# switch-QPC1022.net
KiCad netlist of a schematic drawn in EAGLE
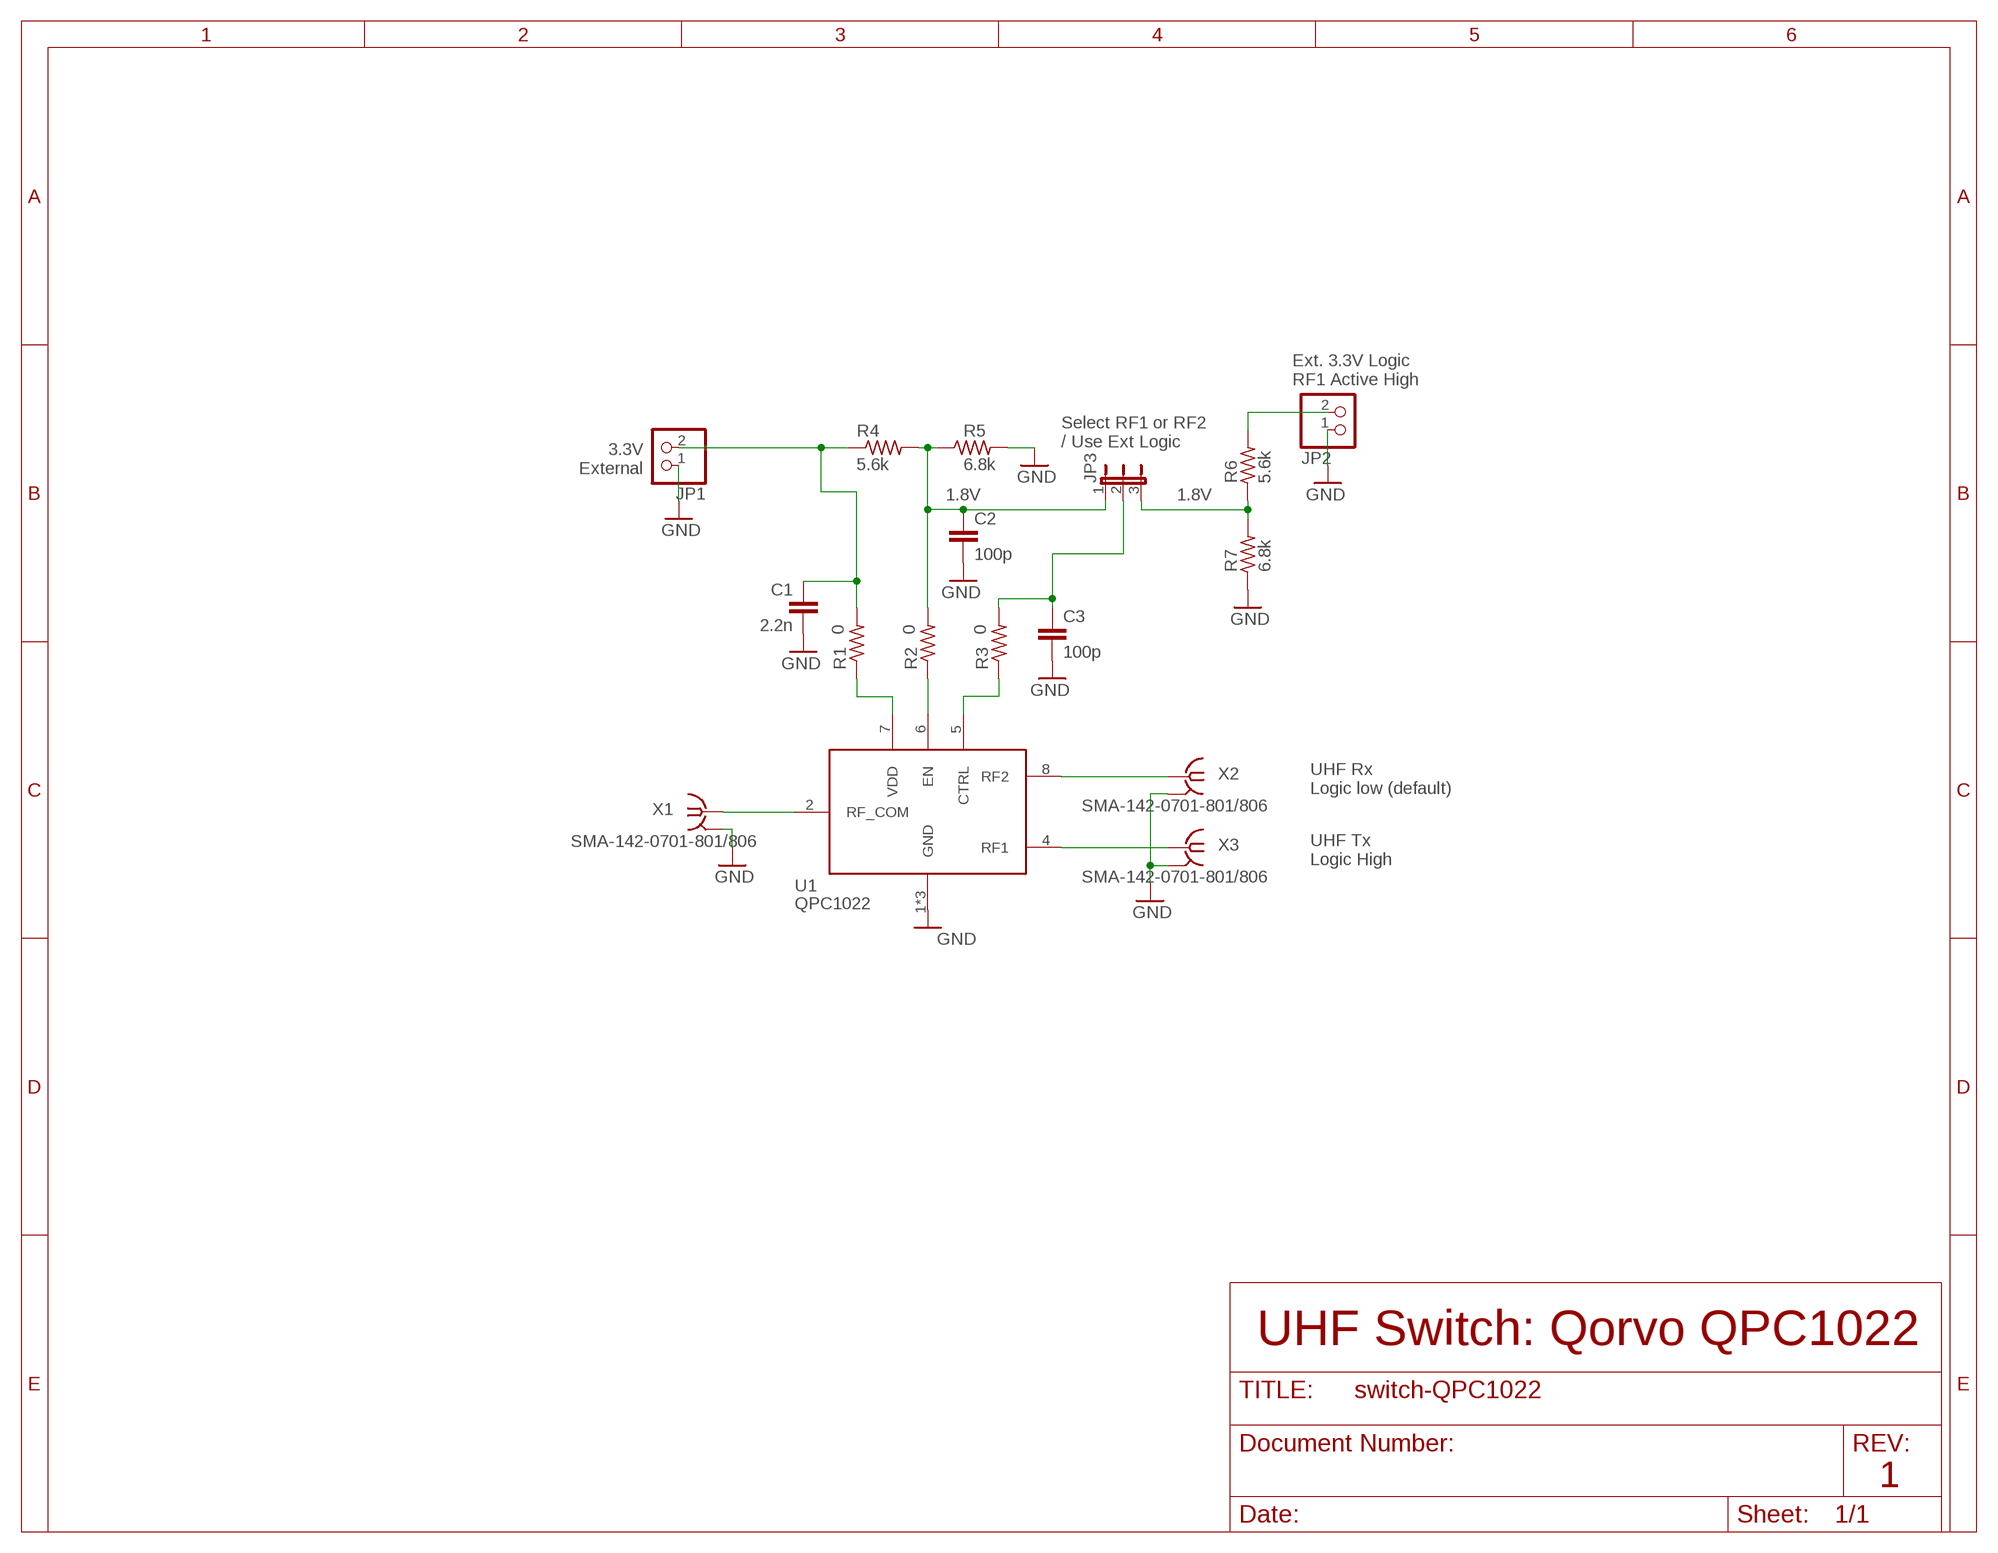
[diagram p0: schematic, sheet 1]

(export (version "E")
  (design (tool "Eeschema 10.0.6"))
  (components
    (comp (ref "C1")
      (value "2.2n")
      (footprint "eagle-import:.0603-B-NOSILK")
      (libsource (lib "eagle-import") (part "C-EU0603-B-NOSILK"))
    )
    (comp (ref "C2")
      (value "100p")
      (footprint "eagle-import:.0402-B-NOSILK")
      (libsource (lib "eagle-import") (part "C-EU0402-B-NOSILK"))
    )
    (comp (ref "C3")
      (value "100p")
      (footprint "eagle-import:.0402-B-NOSILK")
      (libsource (lib "eagle-import") (part "C-EU0402-B-NOSILK"))
    )
    (comp (ref "JP1")
      (value "PINHD-1X2")
      (footprint "eagle-import:1X02")
      (libsource (lib "eagle-import") (part "PINHD-1X2"))
    )
    (comp (ref "JP2")
      (value "PINHD-1X2")
      (footprint "eagle-import:1X02")
      (libsource (lib "eagle-import") (part "PINHD-1X2"))
    )
    (comp (ref "JP3")
      (value "JP2E")
      (footprint "eagle-import:JP2")
      (libsource (lib "eagle-import") (part "JP2E"))
    )
    (comp (ref "R1")
      (value "0")
      (footprint "eagle-import:.0402-B-NOSILK")
      (libsource (lib "eagle-import") (part "R-US_0402-B-NOSILK"))
    )
    (comp (ref "R2")
      (value "0")
      (footprint "eagle-import:.0402-B-NOSILK")
      (libsource (lib "eagle-import") (part "R-US_0402-B-NOSILK"))
    )
    (comp (ref "R3")
      (value "0")
      (footprint "eagle-import:.0402-B-NOSILK")
      (libsource (lib "eagle-import") (part "R-US_0402-B-NOSILK"))
    )
    (comp (ref "R4")
      (value "5.6k")
      (footprint "eagle-import:.0402-B-NOSILK")
      (libsource (lib "eagle-import") (part "R-US_0402-B-NOSILK"))
    )
    (comp (ref "R5")
      (value "6.8k")
      (footprint "eagle-import:.0402-B-NOSILK")
      (libsource (lib "eagle-import") (part "R-US_0402-B-NOSILK"))
    )
    (comp (ref "R6")
      (value "5.6k")
      (footprint "eagle-import:.0402-B-NOSILK")
      (libsource (lib "eagle-import") (part "R-US_0402-B-NOSILK"))
    )
    (comp (ref "R7")
      (value "6.8k")
      (footprint "eagle-import:.0402-B-NOSILK")
      (libsource (lib "eagle-import") (part "R-US_0402-B-NOSILK"))
    )
    (comp (ref "U1")
      (value "QPC1022")
      (footprint "eagle-import:QPC1022")
      (fields (field (name "MFR") "Qorvo"))
      (libsource (lib "eagle-import") (part "QPC1022"))
    )
    (comp (ref "X1")
      (value "SMA-142-0701-801/806")
      (footprint "eagle-import:J502-ND-142-0701-801_806")
      (fields (field (name "MF") "JOHNSON COMPONENTS") (field (name "MPN") "142-0701-801"))
      (libsource (lib "eagle-import") (part "SMA-142-0701-801/806"))
    )
    (comp (ref "X2")
      (value "SMA-142-0701-801/806")
      (footprint "eagle-import:J502-ND-142-0701-801_806")
      (fields (field (name "MF") "JOHNSON COMPONENTS") (field (name "MPN") "142-0701-801"))
      (libsource (lib "eagle-import") (part "SMA-142-0701-801/806"))
    )
    (comp (ref "X3")
      (value "SMA-142-0701-801/806")
      (footprint "eagle-import:J502-ND-142-0701-801_806")
      (fields (field (name "MF") "JOHNSON COMPONENTS") (field (name "MPN") "142-0701-801"))
      (libsource (lib "eagle-import") (part "SMA-142-0701-801/806"))
    )
  )
  (nets
    (net (code "1") (name "GND") (class "Default")
      (node (ref "C1") (pin "2") (pinfunction "2_2") (pintype "passive"))
      (node (ref "C2") (pin "2") (pinfunction "2_2") (pintype "passive"))
      (node (ref "C3") (pin "2") (pinfunction "2_2") (pintype "passive"))
      (node (ref "JP1") (pin "1") (pinfunction "1_1") (pintype "passive"))
      (node (ref "JP2") (pin "1") (pinfunction "1_1") (pintype "passive"))
      (node (ref "R5") (pin "2") (pinfunction "2_2") (pintype "passive"))
      (node (ref "R7") (pin "1") (pinfunction "1_1") (pintype "passive"))
      (node (ref "U1") (pin "1") (pinfunction "GND_1") (pintype "power_in"))
      (node (ref "U1") (pin "3") (pinfunction "GND_3") (pintype "power_in"))
      (node (ref "U1") (pin "9") (pinfunction "GND_9") (pintype "power_in"))
      (node (ref "X1") (pin "G@1") (pinfunction "2_G@1") (pintype "passive"))
      (node (ref "X1") (pin "G@2") (pinfunction "2_G@2") (pintype "passive"))
      (node (ref "X1") (pin "G@3") (pinfunction "2_G@3") (pintype "passive"))
      (node (ref "X1") (pin "G@4") (pinfunction "2_G@4") (pintype "passive"))
      (node (ref "X2") (pin "G@1") (pinfunction "2_G@1") (pintype "passive"))
      (node (ref "X2") (pin "G@2") (pinfunction "2_G@2") (pintype "passive"))
      (node (ref "X2") (pin "G@3") (pinfunction "2_G@3") (pintype "passive"))
      (node (ref "X2") (pin "G@4") (pinfunction "2_G@4") (pintype "passive"))
      (node (ref "X3") (pin "G@1") (pinfunction "2_G@1") (pintype "passive"))
      (node (ref "X3") (pin "G@2") (pinfunction "2_G@2") (pintype "passive"))
      (node (ref "X3") (pin "G@3") (pinfunction "2_G@3") (pintype "passive"))
      (node (ref "X3") (pin "G@4") (pinfunction "2_G@4") (pintype "passive"))
    )
    (net (code "2") (name "Net-(C1-Pad1)") (class "Default")
      (node (ref "C1") (pin "1") (pinfunction "1_1") (pintype "passive"))
      (node (ref "JP1") (pin "2") (pinfunction "2_2") (pintype "passive"))
      (node (ref "R1") (pin "2") (pinfunction "2_2") (pintype "passive"))
      (node (ref "R4") (pin "1") (pinfunction "1_1") (pintype "passive"))
    )
    (net (code "3") (name "Net-(C2-Pad1)") (class "Default")
      (node (ref "C2") (pin "1") (pinfunction "1_1") (pintype "passive"))
      (node (ref "JP3") (pin "1") (pinfunction "1_1") (pintype "passive"))
      (node (ref "R2") (pin "2") (pinfunction "2_2") (pintype "passive"))
      (node (ref "R4") (pin "2") (pinfunction "2_2") (pintype "passive"))
      (node (ref "R5") (pin "1") (pinfunction "1_1") (pintype "passive"))
    )
    (net (code "4") (name "Net-(C3-Pad1)") (class "Default")
      (node (ref "C3") (pin "1") (pinfunction "1_1") (pintype "passive"))
      (node (ref "JP3") (pin "2") (pinfunction "2_2") (pintype "passive"))
      (node (ref "R3") (pin "2") (pinfunction "2_2") (pintype "passive"))
    )
    (net (code "5") (name "Net-(JP2-Pad2)") (class "Default")
      (node (ref "JP2") (pin "2") (pinfunction "2_2") (pintype "passive"))
      (node (ref "R6") (pin "2") (pinfunction "2_2") (pintype "passive"))
    )
    (net (code "6") (name "Net-(JP3-Pad3)") (class "Default")
      (node (ref "JP3") (pin "3") (pinfunction "3_3") (pintype "passive"))
      (node (ref "R6") (pin "1") (pinfunction "1_1") (pintype "passive"))
      (node (ref "R7") (pin "2") (pinfunction "2_2") (pintype "passive"))
    )
    (net (code "7") (name "Net-(U1-CTRL)") (class "Default")
      (node (ref "R3") (pin "1") (pinfunction "1_1") (pintype "passive"))
      (node (ref "U1") (pin "5") (pinfunction "CTRL_5") (pintype "bidirectional"))
    )
    (net (code "8") (name "Net-(U1-EN)") (class "Default")
      (node (ref "R2") (pin "1") (pinfunction "1_1") (pintype "passive"))
      (node (ref "U1") (pin "6") (pinfunction "EN_6") (pintype "bidirectional"))
    )
    (net (code "9") (name "Net-(U1-RF1)") (class "Default")
      (node (ref "U1") (pin "4") (pinfunction "RF1_4") (pintype "bidirectional"))
      (node (ref "X3") (pin "1") (pinfunction "1_1") (pintype "passive"))
    )
    (net (code "10") (name "Net-(U1-RF2)") (class "Default")
      (node (ref "U1") (pin "8") (pinfunction "RF2_8") (pintype "bidirectional"))
      (node (ref "X2") (pin "1") (pinfunction "1_1") (pintype "passive"))
    )
    (net (code "11") (name "Net-(U1-RF_COM)") (class "Default")
      (node (ref "U1") (pin "2") (pinfunction "RF_COM_2") (pintype "bidirectional"))
      (node (ref "X1") (pin "1") (pinfunction "1_1") (pintype "passive"))
    )
    (net (code "12") (name "Net-(U1-VDD)") (class "Default")
      (node (ref "R1") (pin "1") (pinfunction "1_1") (pintype "passive"))
      (node (ref "U1") (pin "7") (pinfunction "VDD_7") (pintype "power_in"))
    )
  )
)
